# Battery_Manager.net
KiCad netlist of a schematic drawn in Altium Designer
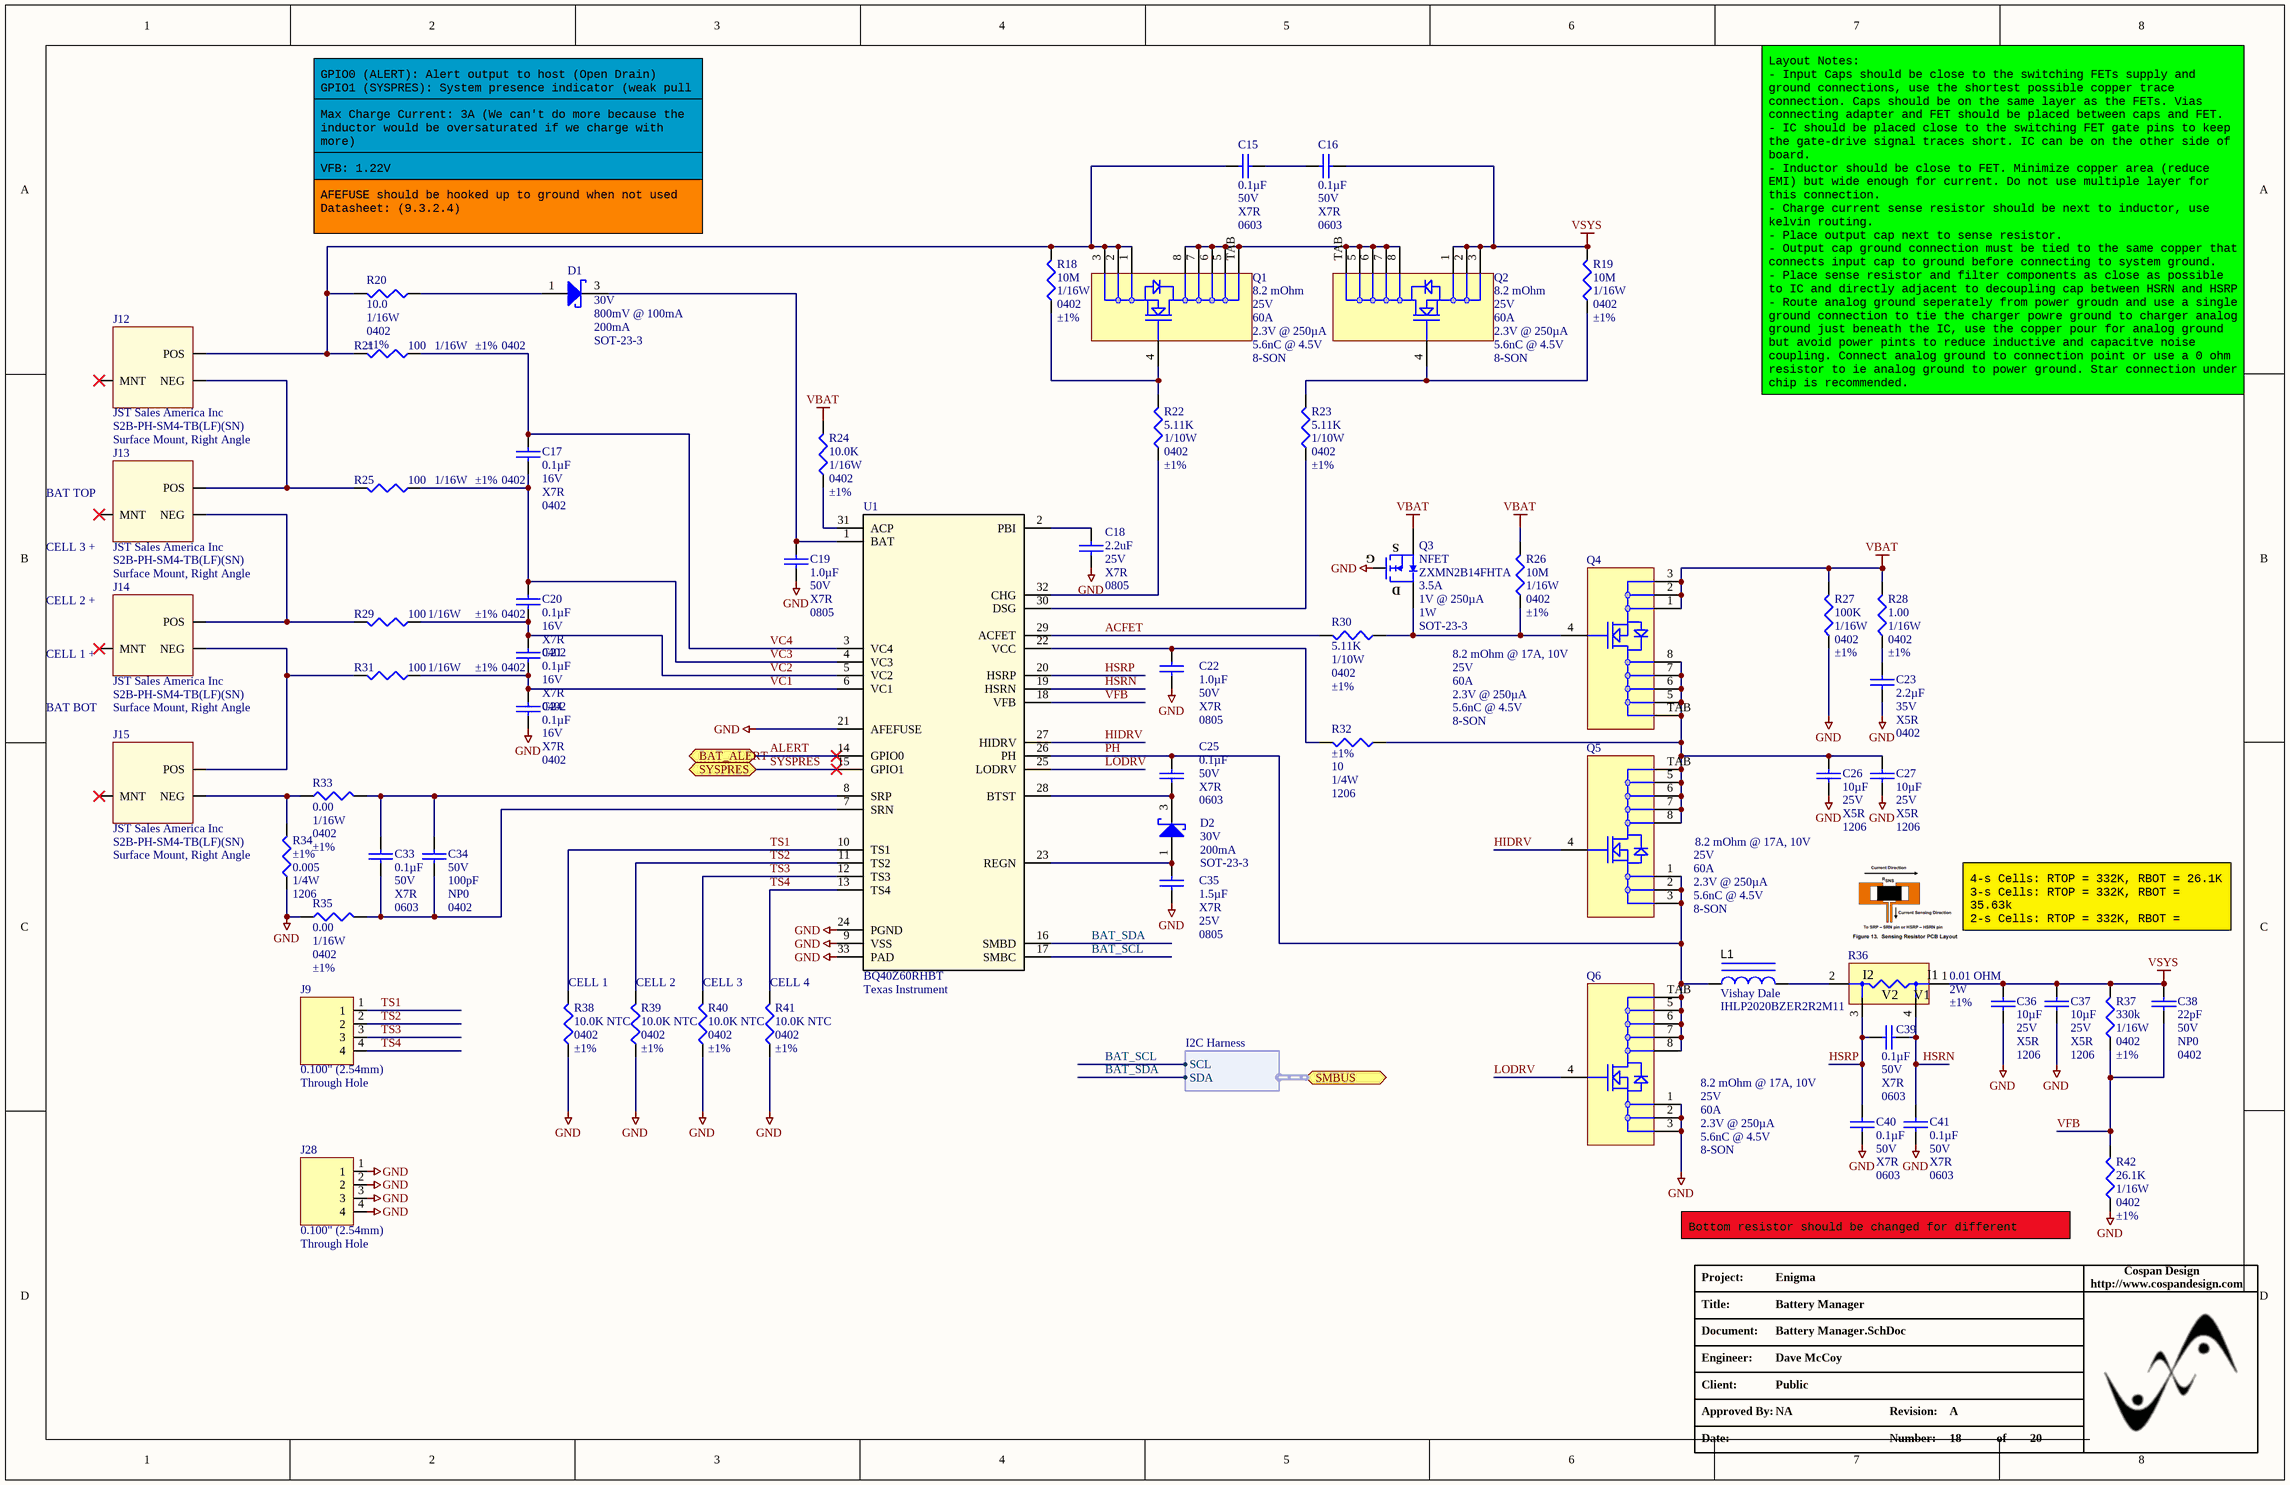
[diagram p0: Battery Manager.SchDoc]

(export (version "E")
  (design (tool "Eeschema 10.0.6"))
  (components
    (comp (ref "C15")
      (value "C_0603_0.1µF")
      (footprint "C_ERA-0603")
      (description "CAP CER 0.1UF 50V X7R 0603")
      (fields
        (field (name "MANUFACTURER") "Samsung Electro-Mechanics America, Inc.")
        (field (name "MANUFACTURER PART NUMBER") "CL10B104KB8SFNC")
        (field (name "CAPACITANCE") "0.1µF")
        (field (name "VOLTAGE - RATED") "50V")
        (field (name "TEMPERATURE COEFFICIENT") "X7R")
        (field (name "PACKAGE / CASE") "0603")
      )
      (libsource (lib "Cospan Design") (part "C_0603_0.1µF"))
    )
    (comp (ref "C16")
      (value "C_0603_0.1µF")
      (footprint "C_ERA-0603")
      (description "CAP CER 0.1UF 50V X7R 0603")
      (fields
        (field (name "MANUFACTURER") "Samsung Electro-Mechanics America, Inc.")
        (field (name "MANUFACTURER PART NUMBER") "CL10B104KB8SFNC")
        (field (name "CAPACITANCE") "0.1µF")
        (field (name "VOLTAGE - RATED") "50V")
        (field (name "TEMPERATURE COEFFICIENT") "X7R")
        (field (name "PACKAGE / CASE") "0603")
      )
      (libsource (lib "Cospan Design") (part "C_0603_0.1µF"))
    )
    (comp (ref "C17")
      (value "0.1uF")
      (footprint "C_0402")
      (description "CAP CER .10UF 16V X7R 0402")
      (fields
        (field (name "MANUFACTURER") "Murata Electronics North America")
        (field (name "MANUFACTURER PART NUMBER") "GRM155R71C104KA88J")
        (field (name "CAPACITANCE") "0.1µF")
        (field (name "VOLTAGE - RATED") "16V")
        (field (name "TEMPERATURE COEFFICIENT") "X7R")
        (field (name "PACKAGE / CASE") "0402")
      )
      (libsource (lib "Main LibraryX") (part "C_0402_0.1UF_16V"))
    )
    (comp (ref "C18")
      (value "C_0805_2.2uF_25V")
      (footprint "C_ERA-0805")
      (fields
        (field (name "MANUFACTURER") "Taiyo Yuden")
        (field (name "MANUFACTURER PART NUMBER") "TMK212B7225KG-TR")
        (field (name "TOLERANCE") "±10%")
        (field (name "CAPACITANCE") "2.2uF")
        (field (name "VOLTAGE - RATED") "25V")
        (field (name "TEMPERATURE COEFFICIENT") "X7R")
        (field (name "PACKAGE / CASE") "0805")
      )
      (libsource (lib "Cospan Design") (part "C_0805_2.2uF_25V"))
    )
    (comp (ref "C19")
      (value "1.0uF")
      (footprint "C_ERA-0805")
      (description "CAP CER 1UF 50V X7R 0805")
      (fields
        (field (name "MANUFACTURER") "Murata Electronics North America")
        (field (name "MANUFACTURER PART NUMBER") "GRM21BR71H105KA12L")
        (field (name "CAPACITANCE") "1.0µF")
        (field (name "VOLTAGE - RATED") "50V")
        (field (name "TEMPERATURE COEFFICIENT") "X7R")
        (field (name "PACKAGE / CASE") "0805")
      )
      (libsource (lib "Main Library") (part "C_0805_1.0uF_50V"))
    )
    (comp (ref "C20")
      (value "0.1uF")
      (footprint "C_0402")
      (description "CAP CER .10UF 16V X7R 0402")
      (fields
        (field (name "MANUFACTURER") "Murata Electronics North America")
        (field (name "MANUFACTURER PART NUMBER") "GRM155R71C104KA88J")
        (field (name "CAPACITANCE") "0.1µF")
        (field (name "VOLTAGE - RATED") "16V")
        (field (name "TEMPERATURE COEFFICIENT") "X7R")
        (field (name "PACKAGE / CASE") "0402")
      )
      (libsource (lib "Main LibraryX") (part "C_0402_0.1UF_16V"))
    )
    (comp (ref "C21")
      (value "0.1uF")
      (footprint "C_0402")
      (description "CAP CER .10UF 16V X7R 0402")
      (fields
        (field (name "MANUFACTURER") "Murata Electronics North America")
        (field (name "MANUFACTURER PART NUMBER") "GRM155R71C104KA88J")
        (field (name "CAPACITANCE") "0.1µF")
        (field (name "VOLTAGE - RATED") "16V")
        (field (name "TEMPERATURE COEFFICIENT") "X7R")
        (field (name "PACKAGE / CASE") "0402")
      )
      (libsource (lib "Main LibraryX") (part "C_0402_0.1UF_16V"))
    )
    (comp (ref "C22")
      (value "1.0uF")
      (footprint "C_ERA-0805")
      (description "CAP CER 1UF 50V X7R 0805")
      (fields
        (field (name "MANUFACTURER") "Murata Electronics North America")
        (field (name "MANUFACTURER PART NUMBER") "GRM21BR71H105KA12L")
        (field (name "CAPACITANCE") "1.0µF")
        (field (name "VOLTAGE - RATED") "50V")
        (field (name "TEMPERATURE COEFFICIENT") "X7R")
        (field (name "PACKAGE / CASE") "0805")
      )
      (libsource (lib "Main Library") (part "C_0805_1.0uF_50V"))
    )
    (comp (ref "C23")
      (value "C_0402_2.2uF_35V")
      (footprint "C_ERA-0402")
      (description "CAP CER 2.2UF 35V 20% X5R 0402")
      (fields
        (field (name "MANUFACTURER") "TDK Corporation")
        (field (name "MANUFACTURER PART NUMBER") "C1005X5R1V225K050BC")
        (field (name "CAPACITANCE") "2.2µF")
        (field (name "VOLTAGE - RATED") "35V")
        (field (name "TEMPERATURE COEFFICIENT") "X5R")
        (field (name "PACKAGE / CASE") "0402")
      )
      (libsource (lib "Main LibraryX") (part "C_0402_2.2uF_35V"))
    )
    (comp (ref "C24")
      (value "0.1uF")
      (footprint "C_0402")
      (description "CAP CER .10UF 16V X7R 0402")
      (fields
        (field (name "MANUFACTURER") "Murata Electronics North America")
        (field (name "MANUFACTURER PART NUMBER") "GRM155R71C104KA88J")
        (field (name "CAPACITANCE") "0.1µF")
        (field (name "VOLTAGE - RATED") "16V")
        (field (name "TEMPERATURE COEFFICIENT") "X7R")
        (field (name "PACKAGE / CASE") "0402")
      )
      (libsource (lib "Main LibraryX") (part "C_0402_0.1UF_16V"))
    )
    (comp (ref "C25")
      (value "C_0603_0.1µF")
      (footprint "C_ERA-0603")
      (description "CAP CER 0.1UF 50V X7R 0603")
      (fields
        (field (name "MANUFACTURER") "Samsung Electro-Mechanics America, Inc.")
        (field (name "MANUFACTURER PART NUMBER") "CL10B104KB8SFNC")
        (field (name "CAPACITANCE") "0.1µF")
        (field (name "VOLTAGE - RATED") "50V")
        (field (name "TEMPERATURE COEFFICIENT") "X7R")
        (field (name "PACKAGE / CASE") "0603")
      )
      (libsource (lib "Cospan Design") (part "C_0603_0.1µF"))
    )
    (comp (ref "C26")
      (value "10µF")
      (footprint "CAP-1206")
      (description "CAP CER 10UF 25V X5R 1206")
      (fields
        (field (name "MANUFACTURER") "Murata Electronics North America")
        (field (name "MANUFACTURER PART NUMBER") "GRM31CR61E106MA12L")
        (field (name "CAPACITANCE") "10µF")
        (field (name "VOLTAGE - RATED") "25V")
        (field (name "TEMPERATURE COEFFICIENT") "X5R")
        (field (name "PACKAGE / CASE") "1206")
      )
      (libsource (lib "Main Library") (part "C_1206_10UF_25V"))
    )
    (comp (ref "C27")
      (value "10µF")
      (footprint "CAP-1206")
      (description "CAP CER 10UF 25V X5R 1206")
      (fields
        (field (name "MANUFACTURER") "Murata Electronics North America")
        (field (name "MANUFACTURER PART NUMBER") "GRM31CR61E106MA12L")
        (field (name "CAPACITANCE") "10µF")
        (field (name "VOLTAGE - RATED") "25V")
        (field (name "TEMPERATURE COEFFICIENT") "X5R")
        (field (name "PACKAGE / CASE") "1206")
      )
      (libsource (lib "Main Library") (part "C_1206_10UF_25V"))
    )
    (comp (ref "C33")
      (value "C_0603_0.1µF")
      (footprint "C_ERA-0603")
      (description "CAP CER 0.1UF 50V X7R 0603")
      (fields
        (field (name "MANUFACTURER") "Samsung Electro-Mechanics America, Inc.")
        (field (name "MANUFACTURER PART NUMBER") "CL10B104KB8SFNC")
        (field (name "CAPACITANCE") "0.1µF")
        (field (name "VOLTAGE - RATED") "50V")
        (field (name "TEMPERATURE COEFFICIENT") "X7R")
        (field (name "PACKAGE / CASE") "0603")
      )
      (libsource (lib "Cospan Design") (part "C_0603_0.1µF"))
    )
    (comp (ref "C34")
      (value "100pF")
      (footprint "C_0402")
      (description "CAP CER 100PF 50V 5% C0G 0402")
      (fields
        (field (name "MANUFACTURER") "Murata Electronics North America")
        (field (name "MANUFACTURER PART NUMBER") "GRM1555C1H101JA01D")
        (field (name "VOLTAGE - RATED") "50V")
        (field (name "CAPACITANCE") "100pF")
        (field (name "TEMPERATURE COEFFICIENT") "NP0")
        (field (name "PACKAGE / CASE") "0402")
      )
      (libsource (lib "Main LibraryX") (part "C_0402_100PF"))
    )
    (comp (ref "C35")
      (value "C_0805_1.5uF_25V")
      (footprint "C_ERA-0805")
      (description "1.5µF ±10% 25V Ceramic Capacitor X7R 0805 (2012 Metric)")
      (fields
        (field (name "MANUFACTURER") "Murata Electronics North America")
        (field (name "MANUFACTURER PART NUMBER") "GRM21BR71E155KA88L")
        (field (name "CAPACITANCE") "1.5µF")
        (field (name "VOLTAGE - RATED") "X7R")
        (field (name "TEMPERATURE COEFFICIENT") "25V")
        (field (name "PACKAGE / CASE") "0805")
      )
      (libsource (lib "Cospan Design") (part "C_0805_1.5uF_25V"))
    )
    (comp (ref "C36")
      (value "10µF")
      (footprint "CAP-1206")
      (description "CAP CER 10UF 25V X5R 1206")
      (fields
        (field (name "MANUFACTURER") "Murata Electronics North America")
        (field (name "MANUFACTURER PART NUMBER") "GRM31CR61E106MA12L")
        (field (name "CAPACITANCE") "10µF")
        (field (name "VOLTAGE - RATED") "25V")
        (field (name "TEMPERATURE COEFFICIENT") "X5R")
        (field (name "PACKAGE / CASE") "1206")
      )
      (libsource (lib "Main Library") (part "C_1206_10UF_25V"))
    )
    (comp (ref "C37")
      (value "10µF")
      (footprint "CAP-1206")
      (description "CAP CER 10UF 25V X5R 1206")
      (fields
        (field (name "MANUFACTURER") "Murata Electronics North America")
        (field (name "MANUFACTURER PART NUMBER") "GRM31CR61E106MA12L")
        (field (name "CAPACITANCE") "10µF")
        (field (name "VOLTAGE - RATED") "25V")
        (field (name "TEMPERATURE COEFFICIENT") "X5R")
        (field (name "PACKAGE / CASE") "1206")
      )
      (libsource (lib "Main Library") (part "C_1206_10UF_25V"))
    )
    (comp (ref "C38")
      (value "22pF")
      (footprint "C_ERA-0402")
      (description "CAP CER 22PF 50V NP0 0402")
      (fields
        (field (name "MANUFACTURER") "Murata Electronics North America")
        (field (name "MANUFACTURER PART NUMBER") "GRM1555C1H220FA01D")
        (field (name "CAPACITANCE") "22pF")
        (field (name "VOLTAGE - RATED") "50V")
        (field (name "TEMPERATURE COEFFICIENT") "NP0")
        (field (name "PACKAGE / CASE") "0402")
      )
      (libsource (lib "Main LibraryX") (part "C_0402_22PF_50V"))
    )
    (comp (ref "C39")
      (value "C_0603_0.1µF")
      (footprint "C_ERA-0603")
      (description "CAP CER 0.1UF 50V X7R 0603")
      (fields
        (field (name "MANUFACTURER") "Samsung Electro-Mechanics America, Inc.")
        (field (name "MANUFACTURER PART NUMBER") "CL10B104KB8SFNC")
        (field (name "CAPACITANCE") "0.1µF")
        (field (name "VOLTAGE - RATED") "50V")
        (field (name "TEMPERATURE COEFFICIENT") "X7R")
        (field (name "PACKAGE / CASE") "0603")
      )
      (libsource (lib "Cospan Design") (part "C_0603_0.1µF"))
    )
    (comp (ref "C40")
      (value "C_0603_0.1µF")
      (footprint "C_ERA-0603")
      (description "CAP CER 0.1UF 50V X7R 0603")
      (fields
        (field (name "MANUFACTURER") "Samsung Electro-Mechanics America, Inc.")
        (field (name "MANUFACTURER PART NUMBER") "CL10B104KB8SFNC")
        (field (name "CAPACITANCE") "0.1µF")
        (field (name "VOLTAGE - RATED") "50V")
        (field (name "TEMPERATURE COEFFICIENT") "X7R")
        (field (name "PACKAGE / CASE") "0603")
      )
      (libsource (lib "Cospan Design") (part "C_0603_0.1µF"))
    )
    (comp (ref "C41")
      (value "C_0603_0.1µF")
      (footprint "C_ERA-0603")
      (description "CAP CER 0.1UF 50V X7R 0603")
      (fields
        (field (name "MANUFACTURER") "Samsung Electro-Mechanics America, Inc.")
        (field (name "MANUFACTURER PART NUMBER") "CL10B104KB8SFNC")
        (field (name "CAPACITANCE") "0.1µF")
        (field (name "VOLTAGE - RATED") "50V")
        (field (name "TEMPERATURE COEFFICIENT") "X7R")
        (field (name "PACKAGE / CASE") "0603")
      )
      (libsource (lib "Cospan Design") (part "C_0603_0.1µF"))
    )
    (comp (ref "D1")
      (value "BAT54")
      (footprint "SOT23")
      (description "DIODE SCHOTTKY 30V 200MA SOT-23")
      (fields
        (field (name "MANUFACTURER") "Fairchild Semiconductor")
        (field (name "VOLTAGE - DC REVERSE (VR) (MAX)") "30V")
        (field (name "VOLTAGE - FORWARD (VF) (MAX) @ IF") "800mV @ 100mA")
        (field (name "CURRENT - AVERAGE RECTIFIED (IO)") "200mA")
        (field (name "PACKAGE / CASE") "SOT-23-3")
      )
      (libsource (lib "Main Library") (part "D_SCHOTT_BAT54"))
    )
    (comp (ref "D2")
      (value "BAT54")
      (footprint "SOT23")
      (description "DIODE SCHOTTKY 30V 200MA SOT-23")
      (fields
        (field (name "MANUFACTURER") "Fairchild Semiconductor")
        (field (name "VOLTAGE - DC REVERSE (VR) (MAX)") "30V")
        (field (name "CURRENT - AVERAGE RECTIFIED (IO)") "200mA")
        (field (name "PACKAGE / CASE") "SOT-23-3")
      )
      (libsource (lib "Main Library") (part "D_SCHOTT_BAT54"))
    )
    (comp (ref "J9")
      (value "J_HDR1X4_THRHOLE_VERT")
      (footprint "HDR_1X4")
      (description "CONN HEADER .100\" 4POS TIN PCB")
      (fields
        (field (name "MANUFACTURER") "Samtec")
        (field (name "MANUFACTURER PART NUMBER") "TSW-104-07-T-S")
        (field (name "PITCH") "0.100\" (2.54mm)")
        (field (name "MOUNTING TYPE") "Through Hole")
      )
      (libsource (lib "Main Library") (part "J_HDR1X4_THRHOLE_VERT"))
    )
    (comp (ref "J12")
      (value "J_LIPO_BAT_CONNECTOR")
      (footprint "HDR_1X2_LIPO_BATTERY")
      (description "CONN HEADER PH SIDE 2POS 2MM SMD")
      (fields
        (field (name "MANUFACTURER") "JST Sales America Inc")
        (field (name "MANUFACTURER PART NUMBER") "S2B-PH-SM4-TB(LF)(SN)")
        (field (name "MOUNTING TYPE") "Surface Mount, Right Angle")
      )
      (libsource (lib "Main Library") (part "J_LIPO_BAT_CONNECTOR"))
    )
    (comp (ref "J13")
      (value "J_LIPO_BAT_CONNECTOR")
      (footprint "HDR_1X2_LIPO_BATTERY")
      (description "CONN HEADER PH SIDE 2POS 2MM SMD")
      (fields
        (field (name "MANUFACTURER") "JST Sales America Inc")
        (field (name "MANUFACTURER PART NUMBER") "S2B-PH-SM4-TB(LF)(SN)")
        (field (name "MOUNTING TYPE") "Surface Mount, Right Angle")
      )
      (libsource (lib "Main Library") (part "J_LIPO_BAT_CONNECTOR"))
    )
    (comp (ref "J14")
      (value "J_LIPO_BAT_CONNECTOR")
      (footprint "HDR_1X2_LIPO_BATTERY")
      (description "CONN HEADER PH SIDE 2POS 2MM SMD")
      (fields
        (field (name "MANUFACTURER") "JST Sales America Inc")
        (field (name "MANUFACTURER PART NUMBER") "S2B-PH-SM4-TB(LF)(SN)")
        (field (name "MOUNTING TYPE") "Surface Mount, Right Angle")
      )
      (libsource (lib "Main Library") (part "J_LIPO_BAT_CONNECTOR"))
    )
    (comp (ref "J15")
      (value "J_LIPO_BAT_CONNECTOR")
      (footprint "HDR_1X2_LIPO_BATTERY")
      (description "CONN HEADER PH SIDE 2POS 2MM SMD")
      (fields
        (field (name "MANUFACTURER") "JST Sales America Inc")
        (field (name "MANUFACTURER PART NUMBER") "S2B-PH-SM4-TB(LF)(SN)")
        (field (name "MOUNTING TYPE") "Surface Mount, Right Angle")
      )
      (libsource (lib "Main Library") (part "J_LIPO_BAT_CONNECTOR"))
    )
    (comp (ref "J28")
      (value "J_HDR1X4_THRHOLE_VERT")
      (footprint "HDR_1X4")
      (description "CONN HEADER .100\" 4POS TIN PCB")
      (fields
        (field (name "MANUFACTURER") "Samtec")
        (field (name "MANUFACTURER PART NUMBER") "TSW-104-07-T-S")
        (field (name "PITCH") "0.100\" (2.54mm)")
        (field (name "MOUNTING TYPE") "Through Hole")
      )
      (libsource (lib "Main Library") (part "J_HDR1X4_THRHOLE_VERT"))
    )
    (comp (ref "L1")
      (value "L_IHLP2020BZER2R2M11")
      (footprint "IHLP-2020BZ")
      (description "FIXED IND 2.2UH 5A 37.7 MOHM SMD")
      (fields
        (field (name "TOLERANCE") "±20%")
        (field (name "MANUFACTURER") "Vishay Dale")
        (field (name "MANUFACTURER PART NUMBER") "IHLP2020BZER2R2M11")
      )
      (libsource (lib "Cospan Design") (part "L_IHLP2020BZER2R2M11"))
    )
    (comp (ref "Q1")
      (value "N-Channel Nex_FET")
      (footprint "Q_TDSON-8 NexFET")
      (description "MOSFET N-CH 25V 60A 8-SON")
      (fields
        (field (name "MANUFACTURER") "Texas Instruments")
        (field (name "MANUFACTURER PART NUMBER") "CSD16409Q3")
        (field (name "RDS ON (MAX) @ ID, VGS") "8.2 mOhm")
        (field (name "DRAIN TO SOURCE VOLTAGE (VDSS)") "25V")
        (field (name "CURRENT - CONTINUOUS DRAIN (ID) @ 25° C") "60A")
        (field (name "VGS(TH) (MAX) @ ID") "2.3V @ 250µA")
        (field (name "GATE CHARGE (QG) @ VGS") "5.6nC @ 4.5V")
        (field (name "PACKAGE / CASE") "8-SON")
      )
      (libsource (lib "Main Library") (part "Q_N-CH_8SON_60A_9.5mOHM"))
    )
    (comp (ref "Q2")
      (value "N-Channel Nex_FET")
      (footprint "Q_TDSON-8 NexFET")
      (description "MOSFET N-CH 25V 60A 8-SON")
      (fields
        (field (name "MANUFACTURER") "Texas Instruments")
        (field (name "MANUFACTURER PART NUMBER") "CSD16409Q3")
        (field (name "RDS ON (MAX) @ ID, VGS") "8.2 mOhm")
        (field (name "DRAIN TO SOURCE VOLTAGE (VDSS)") "25V")
        (field (name "CURRENT - CONTINUOUS DRAIN (ID) @ 25° C") "60A")
        (field (name "VGS(TH) (MAX) @ ID") "2.3V @ 250µA")
        (field (name "GATE CHARGE (QG) @ VGS") "5.6nC @ 4.5V")
        (field (name "PACKAGE / CASE") "8-SON")
      )
      (libsource (lib "Main Library") (part "Q_N-CH_8SON_60A_9.5mOHM"))
    )
    (comp (ref "Q3")
      (value "NFET")
      (footprint "SOT-23A")
      (description "MOSFET N-CH 20V 3.5A SOT23-3")
      (fields
        (field (name "MANUFACTURER") "Diodes/Zetex")
        (field (name "MANUFACTURER PART NUMBER") "ZXMN2B14FHTA")
        (field (name "CURRENT - CONTINUOUS DRAIN (ID) @ 25° C") "3.5A")
        (field (name "VGS(TH) (MAX) @ ID") "1V @ 250µA")
        (field (name "POWER - MAX") "1W")
        (field (name "PACKAGE / CASE") "SOT-23-3")
      )
      (libsource (lib "Main LibraryX") (part "Q_NFET_3.50A_SOT23"))
    )
    (comp (ref "Q4")
      (value "N-Channel Nex_FET")
      (footprint "Q_TDSON-8 NexFET")
      (description "MOSFET N-CH 25V 60A 8-SON")
      (fields
        (field (name "MANUFACTURER") "Texas Instruments")
        (field (name "MANUFACTURER PART NUMBER") "CSD16409Q3")
        (field (name "RDS ON (MAX) @ ID, VGS") "8.2 mOhm @ 17A, 10V")
        (field (name "DRAIN TO SOURCE VOLTAGE (VDSS)") "25V")
        (field (name "CURRENT - CONTINUOUS DRAIN (ID) @ 25° C") "60A")
        (field (name "VGS(TH) (MAX) @ ID") "2.3V @ 250µA")
        (field (name "GATE CHARGE (QG) @ VGS") "5.6nC @ 4.5V")
        (field (name "PACKAGE / CASE") "8-SON")
      )
      (libsource (lib "Main Library") (part "Q_N-CH_8SON_60A_9.5mOHM"))
    )
    (comp (ref "Q5")
      (value "N-Channel Nex_FET")
      (footprint "Q_TDSON-8 NexFET")
      (description "MOSFET N-CH 25V 60A 8-SON")
      (fields
        (field (name "MANUFACTURER") "Texas Instruments")
        (field (name "MANUFACTURER PART NUMBER") "CSD16409Q3")
        (field (name "RDS ON (MAX) @ ID, VGS") "8.2 mOhm @ 17A, 10V")
        (field (name "DRAIN TO SOURCE VOLTAGE (VDSS)") "25V")
        (field (name "CURRENT - CONTINUOUS DRAIN (ID) @ 25° C") "60A")
        (field (name "VGS(TH) (MAX) @ ID") "2.3V @ 250µA")
        (field (name "GATE CHARGE (QG) @ VGS") "5.6nC @ 4.5V")
        (field (name "PACKAGE / CASE") "8-SON")
      )
      (libsource (lib "Main Library") (part "Q_N-CH_8SON_60A_9.5mOHM"))
    )
    (comp (ref "Q6")
      (value "N-Channel Nex_FET")
      (footprint "Q_TDSON-8 NexFET")
      (description "MOSFET N-CH 25V 60A 8-SON")
      (fields
        (field (name "MANUFACTURER") "Texas Instruments")
        (field (name "MANUFACTURER PART NUMBER") "CSD16409Q3")
        (field (name "RDS ON (MAX) @ ID, VGS") "8.2 mOhm @ 17A, 10V")
        (field (name "DRAIN TO SOURCE VOLTAGE (VDSS)") "25V")
        (field (name "CURRENT - CONTINUOUS DRAIN (ID) @ 25° C") "60A")
        (field (name "VGS(TH) (MAX) @ ID") "2.3V @ 250µA")
        (field (name "GATE CHARGE (QG) @ VGS") "5.6nC @ 4.5V")
        (field (name "PACKAGE / CASE") "8-SON")
      )
      (libsource (lib "Main Library") (part "Q_N-CH_8SON_60A_9.5mOHM"))
    )
    (comp (ref "R18")
      (value "R_0402_10M")
      (footprint "R_0402")
      (description "RES SMD 10M OHM 1% 1/16W 0402")
      (fields
        (field (name "MANUFACTURER") "Yageo")
        (field (name "MANUFACTURER PART NUMBER") "RC0402FR-0710ML")
        (field (name "RESISTANCE IN OHMS") "10M")
        (field (name "POWER (WATTS)") "1/16W")
        (field (name "CASE") "0402")
        (field (name "TOLERANCE") "±1%")
      )
      (libsource (lib "Cospan Design") (part "R_0402_10M"))
    )
    (comp (ref "R19")
      (value "R_0402_10M")
      (footprint "R_0402")
      (description "RES SMD 10M OHM 1% 1/16W 0402")
      (fields
        (field (name "MANUFACTURER") "Yageo")
        (field (name "MANUFACTURER PART NUMBER") "RC0402FR-0710ML")
        (field (name "RESISTANCE IN OHMS") "10M")
        (field (name "POWER (WATTS)") "1/16W")
        (field (name "CASE") "0402")
        (field (name "TOLERANCE") "±1%")
      )
      (libsource (lib "Cospan Design") (part "R_0402_10M"))
    )
    (comp (ref "R20")
      (value "R_0402_10.0")
      (footprint "R_0402")
      (description "RES 10.0 OHM 1/16W 1% 0402 SMD")
      (fields
        (field (name "MANUFACTURER") "Yageo")
        (field (name "MANUFACTURER PART NUMBER") "RC0402FR-0710RL")
        (field (name "RESISTANCE IN OHMS") "10.0")
        (field (name "POWER (WATTS)") "1/16W")
        (field (name "CASE") "0402")
        (field (name "TOLERANCE") "±1%")
      )
      (libsource (lib "Main LibraryX") (part "R_0402_10.0"))
    )
    (comp (ref "R21")
      (value "R_0402_100.0")
      (footprint "R_0402")
      (description "RES 100 OHM 1/16W 1% 0402 SMD")
      (fields
        (field (name "MANUFACTURER") "Yageo")
        (field (name "MANUFACTURER PART NUMBER") "RC0402FR-07100RL")
        (field (name "CASE") "0402")
        (field (name "RESISTANCE IN OHMS") "100")
        (field (name "POWER (WATTS)") "1/16W")
        (field (name "TOLERANCE") "±1%")
      )
      (libsource (lib "Main LibraryX") (part "R_0402_100.0"))
    )
    (comp (ref "R22")
      (value "5.11k Ohms")
      (footprint "R_0402")
      (description "RES 5.11K OHM 1/10W 1% 0402 SMD")
      (fields
        (field (name "MANUFACTURER") "Panasonic - ECG")
        (field (name "MANUFACTURER PART NUMBER") "ERJ-2RKF5111X")
        (field (name "RESISTANCE IN OHMS") "5.11K")
        (field (name "POWER (WATTS)") "1/10W")
        (field (name "CASE") "0402")
        (field (name "TOLERANCE") "±1%")
      )
      (libsource (lib "Main Library") (part "R_0402_5.11K"))
    )
    (comp (ref "R23")
      (value "5.11k Ohms")
      (footprint "R_0402")
      (description "RES 5.11K OHM 1/10W 1% 0402 SMD")
      (fields
        (field (name "MANUFACTURER") "Panasonic - ECG")
        (field (name "MANUFACTURER PART NUMBER") "ERJ-2RKF5111X")
        (field (name "RESISTANCE IN OHMS") "5.11K")
        (field (name "POWER (WATTS)") "1/10W")
        (field (name "CASE") "0402")
        (field (name "TOLERANCE") "±1%")
      )
      (libsource (lib "Main Library") (part "R_0402_5.11K"))
    )
    (comp (ref "R24")
      (value "R_0402_10.0K")
      (footprint "R_0402")
      (description "RES 10.0K OHM 1/16W 1% 0402 SMD")
      (fields
        (field (name "MANUFACTURER") "Stackpole Electronics Inc")
        (field (name "MANUFACTURER PART NUMBER") "RMCF0402FT10K0")
        (field (name "RESISTANCE IN OHMS") "10.0K")
        (field (name "POWER (WATTS)") "1/16W")
        (field (name "CASE") "0402")
        (field (name "TOLERANCE") "±1%")
      )
      (libsource (lib "Main Library") (part "R_0402_10.0K"))
    )
    (comp (ref "R25")
      (value "R_0402_100.0")
      (footprint "R_0402")
      (description "RES 100 OHM 1/16W 1% 0402 SMD")
      (fields
        (field (name "MANUFACTURER") "Yageo")
        (field (name "MANUFACTURER PART NUMBER") "RC0402FR-07100RL")
        (field (name "CASE") "0402")
        (field (name "RESISTANCE IN OHMS") "100")
        (field (name "POWER (WATTS)") "1/16W")
        (field (name "TOLERANCE") "±1%")
      )
      (libsource (lib "Main LibraryX") (part "R_0402_100.0"))
    )
    (comp (ref "R26")
      (value "R_0402_10M")
      (footprint "R_0402")
      (description "RES SMD 10M OHM 1% 1/16W 0402")
      (fields
        (field (name "MANUFACTURER") "Yageo")
        (field (name "MANUFACTURER PART NUMBER") "RC0402FR-0710ML")
        (field (name "RESISTANCE IN OHMS") "10M")
        (field (name "POWER (WATTS)") "1/16W")
        (field (name "CASE") "0402")
        (field (name "TOLERANCE") "±1%")
      )
      (libsource (lib "Cospan Design") (part "R_0402_10M"))
    )
    (comp (ref "R27")
      (value "R_0402_100.0K")
      (footprint "R_0402")
      (description "RES 100K OHM 1/16W 1% 0402 SMD")
      (fields
        (field (name "MANUFACTURER") "Stackpole Electronics Inc")
        (field (name "MANUFACTURER PART NUMBER") "RMCF0402FT100K")
        (field (name "RESISTANCE IN OHMS") "100K")
        (field (name "POWER (WATTS)") "1/16W")
        (field (name "CASE") "0402")
        (field (name "TOLERANCE") "±1%")
      )
      (libsource (lib "Main Library") (part "R_0402_100.0K"))
    )
    (comp (ref "R28")
      (value "1.0 Ohms")
      (footprint "R_0402")
      (description "RES 1.00 OHM 1/16W 1% 0402 SMD")
      (fields
        (field (name "MANUFACTURER") "Yageo")
        (field (name "MANUFACTURER PART NUMBER") "RC0402FR-071RL")
        (field (name "RESISTANCE IN OHMS") "1.00")
        (field (name "POWER (WATTS)") "1/16W")
        (field (name "CASE") "0402")
        (field (name "TOLERANCE") "±1%")
      )
      (libsource (lib "Main Library") (part "R_0402_1.00"))
    )
    (comp (ref "R29")
      (value "R_0402_100.0")
      (footprint "R_0402")
      (description "RES 100 OHM 1/16W 1% 0402 SMD")
      (fields
        (field (name "MANUFACTURER") "Yageo")
        (field (name "MANUFACTURER PART NUMBER") "RC0402FR-07100RL")
        (field (name "CASE") "0402")
        (field (name "RESISTANCE IN OHMS") "100")
        (field (name "POWER (WATTS)") "1/16W")
        (field (name "TOLERANCE") "±1%")
      )
      (libsource (lib "Main LibraryX") (part "R_0402_100.0"))
    )
    (comp (ref "R30")
      (value "5.11k Ohms")
      (footprint "R_0402")
      (description "RES 5.11K OHM 1/10W 1% 0402 SMD")
      (fields
        (field (name "MANUFACTURER") "Panasonic - ECG")
        (field (name "MANUFACTURER PART NUMBER") "ERJ-2RKF5111X")
        (field (name "RESISTANCE IN OHMS") "5.11K")
        (field (name "POWER (WATTS)") "1/10W")
        (field (name "CASE") "0402")
        (field (name "TOLERANCE") "±1%")
      )
      (libsource (lib "Main Library") (part "R_0402_5.11K"))
    )
    (comp (ref "R31")
      (value "R_0402_100.0")
      (footprint "R_0402")
      (description "RES 100 OHM 1/16W 1% 0402 SMD")
      (fields
        (field (name "MANUFACTURER") "Yageo")
        (field (name "MANUFACTURER PART NUMBER") "RC0402FR-07100RL")
        (field (name "CASE") "0402")
        (field (name "RESISTANCE IN OHMS") "100")
        (field (name "POWER (WATTS)") "1/16W")
        (field (name "TOLERANCE") "±1%")
      )
      (libsource (lib "Main LibraryX") (part "R_0402_100.0"))
    )
    (comp (ref "R32")
      (value "R_1206_10")
      (footprint "R_1206")
      (description "RES SMD 10 OHM 1% 1/4W 1206")
      (fields
        (field (name "MANUFACTURER") "Yageo")
        (field (name "MANUFACTURER PART NUMBER") "RC1206FR-0710RL")
        (field (name "TOLERANCE") "±1%")
        (field (name "RESISTANCE IN OHMS") "10")
        (field (name "POWER (WATTS)") "1/4W")
        (field (name "CASE") "1206")
      )
      (libsource (lib "Cospan Design") (part "R_1206_10"))
    )
    (comp (ref "R33")
      (value "0.0 Ohms")
      (footprint "R_0402")
      (description "RES SMD 0.0OHM JUMPER 1/10W 0402")
      (fields
        (field (name "MANUFACTURER") "Panasonic - ECG")
        (field (name "MANUFACTURER PART NUMBER") "ERJ-2GE0R00X")
        (field (name "RESISTANCE IN OHMS") "0.00")
        (field (name "POWER (WATTS)") "1/16W")
        (field (name "CASE") "0402")
        (field (name "TOLERANCE") "±1%")
      )
      (libsource (lib "Main LibraryX") (part "R_0402_0.00"))
    )
    (comp (ref "R34")
      (value "R_1206_0.005")
      (footprint "R_1206")
      (description "RES SMD 0.005 OHM 1% 1W 1206")
      (fields
        (field (name "MANUFACTURER") "Stackpole Electronics Inc.")
        (field (name "MANUFACTURER PART NUMBER") "CSRF1206FT5L00")
        (field (name "TOLERANCE") "±1%")
        (field (name "RESISTANCE IN OHMS") "0.005")
        (field (name "POWER (WATTS)") "1/4W")
        (field (name "CASE") "1206")
      )
      (libsource (lib "Cospan Design") (part "R_1206_0.005"))
    )
    (comp (ref "R35")
      (value "0.0 Ohms")
      (footprint "R_0402")
      (description "RES SMD 0.0OHM JUMPER 1/10W 0402")
      (fields
        (field (name "MANUFACTURER") "Panasonic - ECG")
        (field (name "MANUFACTURER PART NUMBER") "ERJ-2GE0R00X")
        (field (name "RESISTANCE IN OHMS") "0.00")
        (field (name "POWER (WATTS)") "1/16W")
        (field (name "CASE") "0402")
        (field (name "TOLERANCE") "±1%")
      )
      (libsource (lib "Main LibraryX") (part "R_0402_0.00"))
    )
    (comp (ref "R36")
      (value "0.01 OHM")
      (footprint "R_LVK25_0.003")
      (description "RES SMD 0.01 OHM 1% 2W 1224")
      (fields
        (field (name "MANUFACTURER") "Ohmite")
        (field (name "MANUFACTURER PART NUMBER") "LVK25R010FER")
        (field (name "POWER (WATTS)") "2W")
        (field (name "TOLERANCE") "±1%")
      )
      (libsource (lib "Main Library") (part "R_0.010SENSE_LK20"))
    )
    (comp (ref "R37")
      (value "R_0402_330K")
      (footprint "R_0402")
      (description "RES SMD 330K OHM 1% 1/16W 0402")
      (fields
        (field (name "MANUFACTURER") "Yageo")
        (field (name "MANUFACTURER PART NUMBER") "RC0402FR-07330KL")
        (field (name "RESISTANCE IN OHMS") "330k")
        (field (name "POWER (WATTS)") "1/16W")
        (field (name "CASE") "0402")
        (field (name "TOLERANCE") "±1%")
      )
      (libsource (lib "Cospan Design") (part "R_0402_330K"))
    )
    (comp (ref "R38")
      (value "R_0402_NTC_10.0K")
      (footprint "R_0402")
      (description "NTC Thermistor 10k 0402 (1005 Metric)")
      (fields
        (field (name "MANUFACTURER") "Murata Electronics North America")
        (field (name "MANUFACTURER PART NUMBER") "NCP15XH103F03RC")
        (field (name "RESISTANCE IN OHMS") "10.0K NTC")
        (field (name "CASE") "0402")
        (field (name "TOLERANCE") "±1%")
      )
      (libsource (lib "Cospan Design") (part "R_0402_NTC_10.0K"))
    )
    (comp (ref "R39")
      (value "R_0402_NTC_10.0K")
      (footprint "R_0402")
      (description "NTC Thermistor 10k 0402 (1005 Metric)")
      (fields
        (field (name "MANUFACTURER") "Murata Electronics North America")
        (field (name "MANUFACTURER PART NUMBER") "NCP15XH103F03RC")
        (field (name "RESISTANCE IN OHMS") "10.0K NTC")
        (field (name "CASE") "0402")
        (field (name "TOLERANCE") "±1%")
      )
      (libsource (lib "Cospan Design") (part "R_0402_NTC_10.0K"))
    )
    (comp (ref "R40")
      (value "R_0402_NTC_10.0K")
      (footprint "R_0402")
      (description "NTC Thermistor 10k 0402 (1005 Metric)")
      (fields
        (field (name "MANUFACTURER") "Murata Electronics North America")
        (field (name "MANUFACTURER PART NUMBER") "NCP15XH103F03RC")
        (field (name "RESISTANCE IN OHMS") "10.0K NTC")
        (field (name "CASE") "0402")
        (field (name "TOLERANCE") "±1%")
      )
      (libsource (lib "Cospan Design") (part "R_0402_NTC_10.0K"))
    )
    (comp (ref "R41")
      (value "R_0402_NTC_10.0K")
      (footprint "R_0402")
      (description "NTC Thermistor 10k 0402 (1005 Metric)")
      (fields
        (field (name "MANUFACTURER") "Murata Electronics North America")
        (field (name "MANUFACTURER PART NUMBER") "NCP15XH103F03RC")
        (field (name "RESISTANCE IN OHMS") "10.0K NTC")
        (field (name "CASE") "0402")
        (field (name "TOLERANCE") "±1%")
      )
      (libsource (lib "Cospan Design") (part "R_0402_NTC_10.0K"))
    )
    (comp (ref "R42")
      (value "R_0402_26.1K")
      (footprint "R_0402")
      (description "RES SMD 26.1K OHM 1% 1/16W 0402")
      (fields
        (field (name "MANUFACTURER") "Stackpole Electronics Inc.")
        (field (name "MANUFACTURER PART NUMBER") "RMCF0402FT26K1")
        (field (name "RESISTANCE IN OHMS") "26.1K")
        (field (name "POWER (WATTS)") "1/16W")
        (field (name "CASE") "0402")
        (field (name "TOLERANCE") "±1%")
      )
      (libsource (lib "Cospan Design") (part "R_0402_26.1K"))
    )
    (comp (ref "U1")
      (value "U_BQ40Z60RHBR")
      (footprint "RHB0032E")
      (description "IC BATTERY MANAGER 32VQFN")
      (fields
        (field (name "MANUFACTURER PART NUMBER") "BQ40Z60RHBT")
        (field (name "MANUFACTURER") "Texas Instrument")
      )
      (libsource (lib "Cospan Design") (part "U_BQ40Z60RHBR"))
    )
  )
  (nets
    (net (code "3") (name "/ACFET") (class "Default")
      (node (ref "R30") (pin "1") (pinfunction "1_1") (pintype "passive"))
      (node (ref "U1") (pin "29") (pinfunction "ACFET_29") (pintype "passive"))
    )
    (net (code "4") (name "/ALERT") (class "Default")
      (node (ref "U1") (pin "14") (pinfunction "GPIO0_14") (pintype "passive+no_connect"))
    )
    (net (code "5") (name "/BAT_SCL") (class "Default")
      (node (ref "U1") (pin "17") (pinfunction "SMBC_17") (pintype "passive"))
    )
    (net (code "6") (name "/BAT_SDA") (class "Default")
      (node (ref "U1") (pin "16") (pinfunction "SMBD_16") (pintype "passive"))
    )
    (net (code "7") (name "/HIDRV") (class "Default")
      (node (ref "Q5") (pin "4") (pinfunction "G1_4") (pintype "passive"))
      (node (ref "U1") (pin "27") (pinfunction "HIDRV_27") (pintype "passive"))
    )
    (net (code "8") (name "/HSRN") (class "Default")
      (node (ref "C39") (pin "2") (pinfunction "2_2") (pintype "passive"))
      (node (ref "C41") (pin "1") (pinfunction "1_1") (pintype "passive"))
      (node (ref "R36") (pin "4") (pinfunction "V1_4") (pintype "passive"))
      (node (ref "U1") (pin "19") (pinfunction "HSRN_19") (pintype "passive"))
    )
    (net (code "9") (name "/HSRP") (class "Default")
      (node (ref "C39") (pin "1") (pinfunction "1_1") (pintype "passive"))
      (node (ref "C40") (pin "1") (pinfunction "1_1") (pintype "passive"))
      (node (ref "R36") (pin "3") (pinfunction "V2_3") (pintype "passive"))
      (node (ref "U1") (pin "20") (pinfunction "HSRP_20") (pintype "passive"))
    )
    (net (code "10") (name "/LODRV") (class "Default")
      (node (ref "Q6") (pin "4") (pinfunction "G1_4") (pintype "passive"))
      (node (ref "U1") (pin "25") (pinfunction "LODRV_25") (pintype "passive"))
    )
    (net (code "11") (name "/PH") (class "Default")
      (node (ref "C25") (pin "1") (pinfunction "1_1") (pintype "passive"))
      (node (ref "L1") (pin "2") (pinfunction "2_2") (pintype "passive"))
      (node (ref "Q5") (pin "1") (pinfunction "S1_1") (pintype "passive"))
      (node (ref "Q5") (pin "2") (pintype "passive"))
      (node (ref "Q5") (pin "3") (pintype "passive"))
      (node (ref "Q6") (pin "5") (pintype "passive"))
      (node (ref "Q6") (pin "6") (pintype "passive"))
      (node (ref "Q6") (pin "7") (pinfunction "D2a_7") (pintype "passive"))
      (node (ref "Q6") (pin "8") (pinfunction "D2b_8") (pintype "passive"))
      (node (ref "Q6") (pin "TAB") (pintype "passive"))
      (node (ref "U1") (pin "26") (pinfunction "PH_26") (pintype "passive"))
    )
    (net (code "12") (name "/SYSPRES") (class "Default")
      (node (ref "U1") (pin "15") (pinfunction "GPIO1_15") (pintype "passive+no_connect"))
    )
    (net (code "13") (name "/TS1") (class "Default")
      (node (ref "J9") (pin "1") (pinfunction "1_1") (pintype "passive"))
      (node (ref "R38") (pin "1") (pinfunction "1_1") (pintype "passive"))
      (node (ref "U1") (pin "10") (pinfunction "TS1_10") (pintype "passive"))
    )
    (net (code "14") (name "/TS2") (class "Default")
      (node (ref "J9") (pin "2") (pinfunction "2_2") (pintype "passive"))
      (node (ref "R39") (pin "1") (pinfunction "1_1") (pintype "passive"))
      (node (ref "U1") (pin "11") (pinfunction "TS2_11") (pintype "passive"))
    )
    (net (code "15") (name "/TS3") (class "Default")
      (node (ref "J9") (pin "3") (pinfunction "3_3") (pintype "passive"))
      (node (ref "R40") (pin "1") (pinfunction "1_1") (pintype "passive"))
      (node (ref "U1") (pin "12") (pinfunction "TS3_12") (pintype "passive"))
    )
    (net (code "16") (name "/TS4") (class "Default")
      (node (ref "J9") (pin "4") (pinfunction "4_4") (pintype "passive"))
      (node (ref "R41") (pin "1") (pinfunction "1_1") (pintype "passive"))
      (node (ref "U1") (pin "13") (pinfunction "TS4_13") (pintype "passive"))
    )
    (net (code "17") (name "/VC1") (class "Default")
      (node (ref "C21") (pin "2") (pinfunction "2_2") (pintype "passive"))
      (node (ref "C24") (pin "1") (pinfunction "1_1") (pintype "passive"))
      (node (ref "R31") (pin "2") (pinfunction "2_2") (pintype "passive"))
      (node (ref "U1") (pin "6") (pinfunction "VC1_6") (pintype "passive"))
    )
    (net (code "18") (name "/VC2") (class "Default")
      (node (ref "C20") (pin "2") (pinfunction "2_2") (pintype "passive"))
      (node (ref "C21") (pin "1") (pinfunction "1_1") (pintype "passive"))
      (node (ref "R29") (pin "2") (pinfunction "2_2") (pintype "passive"))
      (node (ref "U1") (pin "5") (pinfunction "VC2_5") (pintype "passive"))
    )
    (net (code "19") (name "/VC3") (class "Default")
      (node (ref "C17") (pin "2") (pinfunction "2_2") (pintype "passive"))
      (node (ref "C20") (pin "1") (pinfunction "1_1") (pintype "passive"))
      (node (ref "R25") (pin "2") (pinfunction "2_2") (pintype "passive"))
      (node (ref "U1") (pin "4") (pinfunction "VC3_4") (pintype "passive"))
    )
    (net (code "20") (name "/VC4") (class "Default")
      (node (ref "C17") (pin "1") (pinfunction "1_1") (pintype "passive"))
      (node (ref "R21") (pin "2") (pinfunction "2_2") (pintype "passive"))
      (node (ref "U1") (pin "3") (pinfunction "VC4_3") (pintype "passive"))
    )
    (net (code "21") (name "/VFB") (class "Default")
      (node (ref "C38") (pin "1") (pinfunction "1_1") (pintype "passive"))
      (node (ref "R37") (pin "2") (pinfunction "2_2") (pintype "passive"))
      (node (ref "R42") (pin "1") (pinfunction "1_1") (pintype "passive"))
      (node (ref "U1") (pin "18") (pinfunction "VFB_18") (pintype "passive"))
    )
    (net (code "23") (name "GND") (class "Default")
      (node (ref "C18") (pin "1") (pinfunction "1_1") (pintype "passive"))
      (node (ref "C19") (pin "1") (pinfunction "1_1") (pintype "passive"))
      (node (ref "C22") (pin "1") (pinfunction "1_1") (pintype "passive"))
      (node (ref "C23") (pin "1") (pinfunction "1_1") (pintype "passive"))
      (node (ref "C24") (pin "2") (pinfunction "2_2") (pintype "passive"))
      (node (ref "C26") (pin "1") (pinfunction "1_1") (pintype "passive"))
      (node (ref "C27") (pin "1") (pinfunction "1_1") (pintype "passive"))
      (node (ref "C35") (pin "1") (pinfunction "1_1") (pintype "passive"))
      (node (ref "C36") (pin "2") (pinfunction "2_2") (pintype "passive"))
      (node (ref "C37") (pin "2") (pinfunction "2_2") (pintype "passive"))
      (node (ref "C40") (pin "2") (pinfunction "2_2") (pintype "passive"))
      (node (ref "C41") (pin "2") (pinfunction "2_2") (pintype "passive"))
      (node (ref "J28") (pin "1") (pinfunction "1_1") (pintype "passive"))
      (node (ref "J28") (pin "2") (pinfunction "2_2") (pintype "passive"))
      (node (ref "J28") (pin "3") (pinfunction "3_3") (pintype "passive"))
      (node (ref "J28") (pin "4") (pinfunction "4_4") (pintype "passive"))
      (node (ref "Q3") (pin "1") (pinfunction "G_1") (pintype "passive"))
      (node (ref "Q6") (pin "1") (pinfunction "S1_1") (pintype "passive"))
      (node (ref "Q6") (pin "2") (pintype "passive"))
      (node (ref "Q6") (pin "3") (pintype "passive"))
      (node (ref "R27") (pin "2") (pinfunction "2_2") (pintype "passive"))
      (node (ref "R34") (pin "2") (pinfunction "2_2") (pintype "passive"))
      (node (ref "R35") (pin "2") (pinfunction "2_2") (pintype "passive"))
      (node (ref "R38") (pin "2") (pinfunction "2_2") (pintype "passive"))
      (node (ref "R39") (pin "2") (pinfunction "2_2") (pintype "passive"))
      (node (ref "R40") (pin "2") (pinfunction "2_2") (pintype "passive"))
      (node (ref "R41") (pin "2") (pinfunction "2_2") (pintype "passive"))
      (node (ref "R42") (pin "2") (pinfunction "2_2") (pintype "passive"))
      (node (ref "U1") (pin "21") (pinfunction "AFEFUSE_21") (pintype "passive"))
      (node (ref "U1") (pin "24") (pinfunction "PGND_24") (pintype "passive"))
      (node (ref "U1") (pin "33") (pinfunction "PAD_33") (pintype "passive"))
      (node (ref "U1") (pin "9") (pinfunction "VSS_9") (pintype "passive"))
    )
    (net (code "24") (name "Net-(C15-Pad1)") (class "Default")
      (node (ref "C15") (pin "1") (pinfunction "1_1") (pintype "passive"))
      (node (ref "C16") (pin "2") (pinfunction "2_2") (pintype "passive"))
    )
    (net (code "25") (name "Net-(C23-Pad2)") (class "Default")
      (node (ref "C23") (pin "2") (pinfunction "2_2") (pintype "passive"))
      (node (ref "R28") (pin "2") (pinfunction "2_2") (pintype "passive"))
    )
    (net (code "26") (name "Net-(D1-A)") (class "Default")
      (node (ref "D1") (pin "1") (pinfunction "A_1") (pintype "passive"))
      (node (ref "R20") (pin "2") (pinfunction "2_2") (pintype "passive"))
    )
    (net (code "27") (name "Net-(D1-K)") (class "Default")
      (node (ref "C19") (pin "2") (pinfunction "2_2") (pintype "passive"))
      (node (ref "D1") (pin "3") (pinfunction "K_3") (pintype "passive"))
      (node (ref "U1") (pin "1") (pinfunction "BAT_1") (pintype "passive"))
    )
    (net (code "28") (name "Net-(D2-A)") (class "Default")
      (node (ref "C35") (pin "2") (pinfunction "2_2") (pintype "passive"))
      (node (ref "D2") (pin "1") (pinfunction "A_1") (pintype "passive"))
      (node (ref "U1") (pin "23") (pinfunction "REGN_23") (pintype "passive"))
    )
    (net (code "29") (name "Net-(D2-K)") (class "Default")
      (node (ref "C25") (pin "2") (pinfunction "2_2") (pintype "passive"))
      (node (ref "D2") (pin "3") (pinfunction "K_3") (pintype "passive"))
      (node (ref "U1") (pin "28") (pinfunction "BTST_28") (pintype "passive"))
    )
    (net (code "30") (name "Net-(J12-NEG)") (class "Default")
      (node (ref "J12") (pin "2") (pinfunction "NEG_2") (pintype "passive"))
      (node (ref "J13") (pin "1") (pinfunction "POS_1") (pintype "passive"))
      (node (ref "R25") (pin "1") (pinfunction "1_1") (pintype "passive"))
    )
    (net (code "31") (name "Net-(J12-POS)") (class "Default")
      (node (ref "C15") (pin "2") (pinfunction "2_2") (pintype "passive"))
      (node (ref "J12") (pin "1") (pinfunction "POS_1") (pintype "passive"))
      (node (ref "Q1") (pin "1") (pinfunction "S1_1") (pintype "passive"))
      (node (ref "Q1") (pin "2") (pintype "passive"))
      (node (ref "Q1") (pin "3") (pintype "passive"))
      (node (ref "R18") (pin "1") (pinfunction "1_1") (pintype "passive"))
      (node (ref "R20") (pin "1") (pinfunction "1_1") (pintype "passive"))
      (node (ref "R21") (pin "1") (pinfunction "1_1") (pintype "passive"))
    )
    (net (code "32") (name "Net-(J13-NEG)") (class "Default")
      (node (ref "J13") (pin "2") (pinfunction "NEG_2") (pintype "passive"))
      (node (ref "J14") (pin "1") (pinfunction "POS_1") (pintype "passive"))
      (node (ref "R29") (pin "1") (pinfunction "1_1") (pintype "passive"))
    )
    (net (code "33") (name "Net-(J14-NEG)") (class "Default")
      (node (ref "J14") (pin "2") (pinfunction "NEG_2") (pintype "passive"))
      (node (ref "J15") (pin "1") (pinfunction "POS_1") (pintype "passive"))
      (node (ref "R31") (pin "1") (pinfunction "1_1") (pintype "passive"))
    )
    (net (code "34") (name "Net-(J15-NEG)") (class "Default")
      (node (ref "J15") (pin "2") (pinfunction "NEG_2") (pintype "passive"))
      (node (ref "R33") (pin "2") (pinfunction "2_2") (pintype "passive"))
      (node (ref "R34") (pin "1") (pinfunction "1_1") (pintype "passive"))
    )
    (net (code "35") (name "Net-(Q1-D2a)") (class "Default")
      (node (ref "Q1") (pin "5") (pintype "passive"))
      (node (ref "Q1") (pin "6") (pintype "passive"))
      (node (ref "Q1") (pin "7") (pinfunction "D2a_7") (pintype "passive"))
      (node (ref "Q1") (pin "8") (pinfunction "D2b_8") (pintype "passive"))
      (node (ref "Q1") (pin "TAB") (pintype "passive"))
      (node (ref "Q2") (pin "5") (pintype "passive"))
      (node (ref "Q2") (pin "6") (pintype "passive"))
      (node (ref "Q2") (pin "7") (pinfunction "D2a_7") (pintype "passive"))
      (node (ref "Q2") (pin "8") (pinfunction "D2b_8") (pintype "passive"))
      (node (ref "Q2") (pin "TAB") (pintype "passive"))
    )
    (net (code "36") (name "Net-(Q1-G1)") (class "Default")
      (node (ref "Q1") (pin "4") (pinfunction "G1_4") (pintype "passive"))
      (node (ref "R18") (pin "2") (pinfunction "2_2") (pintype "passive"))
      (node (ref "R22") (pin "1") (pinfunction "1_1") (pintype "passive"))
    )
    (net (code "37") (name "Net-(Q2-G1)") (class "Default")
      (node (ref "Q2") (pin "4") (pinfunction "G1_4") (pintype "passive"))
      (node (ref "R19") (pin "2") (pinfunction "2_2") (pintype "passive"))
      (node (ref "R23") (pin "1") (pinfunction "1_1") (pintype "passive"))
    )
    (net (code "38") (name "Net-(Q3-D)") (class "Default")
      (node (ref "Q3") (pin "3") (pinfunction "D_3") (pintype "passive"))
      (node (ref "Q4") (pin "4") (pinfunction "G1_4") (pintype "passive"))
      (node (ref "R26") (pin "2") (pinfunction "2_2") (pintype "passive"))
      (node (ref "R30") (pin "2") (pinfunction "2_2") (pintype "passive"))
    )
    (net (code "39") (name "Net-(Q4-D2a)") (class "Default")
      (node (ref "C26") (pin "2") (pinfunction "2_2") (pintype "passive"))
      (node (ref "C27") (pin "2") (pinfunction "2_2") (pintype "passive"))
      (node (ref "Q4") (pin "5") (pintype "passive"))
      (node (ref "Q4") (pin "6") (pintype "passive"))
      (node (ref "Q4") (pin "7") (pinfunction "D2a_7") (pintype "passive"))
      (node (ref "Q4") (pin "8") (pinfunction "D2b_8") (pintype "passive"))
      (node (ref "Q4") (pin "TAB") (pintype "passive"))
      (node (ref "Q5") (pin "5") (pintype "passive"))
      (node (ref "Q5") (pin "6") (pintype "passive"))
      (node (ref "Q5") (pin "7") (pinfunction "D2a_7") (pintype "passive"))
      (node (ref "Q5") (pin "8") (pinfunction "D2b_8") (pintype "passive"))
      (node (ref "Q5") (pin "TAB") (pintype "passive"))
      (node (ref "R32") (pin "2") (pinfunction "2_2") (pintype "passive"))
    )
    (net (code "40") (name "Net-(R36-I2)") (class "Default")
      (node (ref "L1") (pin "1") (pinfunction "1_1") (pintype "passive"))
      (node (ref "R36") (pin "2") (pinfunction "I2_2") (pintype "passive"))
    )
    (net (code "41") (name "Net-(U1-ACP)") (class "Default")
      (node (ref "R24") (pin "2") (pinfunction "2_2") (pintype "passive"))
      (node (ref "U1") (pin "31") (pinfunction "ACP_31") (pintype "passive"))
    )
    (net (code "42") (name "Net-(U1-CHG)") (class "Default")
      (node (ref "R22") (pin "2") (pinfunction "2_2") (pintype "passive"))
      (node (ref "U1") (pin "32") (pinfunction "CHG_32") (pintype "passive"))
    )
    (net (code "43") (name "Net-(U1-DSG)") (class "Default")
      (node (ref "R23") (pin "2") (pinfunction "2_2") (pintype "passive"))
      (node (ref "U1") (pin "30") (pinfunction "DSG_30") (pintype "passive"))
    )
    (net (code "44") (name "Net-(U1-PBI)") (class "Default")
      (node (ref "C18") (pin "2") (pinfunction "2_2") (pintype "passive"))
      (node (ref "U1") (pin "2") (pinfunction "PBI_2") (pintype "passive"))
    )
    (net (code "45") (name "Net-(U1-SRN)") (class "Default")
      (node (ref "C33") (pin "1") (pinfunction "1_1") (pintype "passive"))
      (node (ref "C34") (pin "1") (pinfunction "1_1") (pintype "passive"))
      (node (ref "R35") (pin "1") (pinfunction "1_1") (pintype "passive"))
      (node (ref "U1") (pin "7") (pinfunction "SRN_7") (pintype "passive"))
    )
    (net (code "46") (name "Net-(U1-SRP)") (class "Default")
      (node (ref "C33") (pin "2") (pinfunction "2_2") (pintype "passive"))
      (node (ref "C34") (pin "2") (pinfunction "2_2") (pintype "passive"))
      (node (ref "R33") (pin "1") (pinfunction "1_1") (pintype "passive"))
      (node (ref "U1") (pin "8") (pinfunction "SRP_8") (pintype "passive"))
    )
    (net (code "47") (name "Net-(U1-VCC)") (class "Default")
      (node (ref "C22") (pin "2") (pinfunction "2_2") (pintype "passive"))
      (node (ref "R32") (pin "1") (pinfunction "1_1") (pintype "passive"))
      (node (ref "U1") (pin "22") (pinfunction "VCC_22") (pintype "passive"))
    )
    (net (code "48") (name "VBAT") (class "Default")
      (node (ref "Q3") (pin "2") (pinfunction "S_2") (pintype "passive"))
      (node (ref "Q4") (pin "1") (pinfunction "S1_1") (pintype "passive"))
      (node (ref "Q4") (pin "2") (pintype "passive"))
      (node (ref "Q4") (pin "3") (pintype "passive"))
      (node (ref "R24") (pin "1") (pinfunction "1_1") (pintype "passive"))
      (node (ref "R26") (pin "1") (pinfunction "1_1") (pintype "passive"))
      (node (ref "R27") (pin "1") (pinfunction "1_1") (pintype "passive"))
      (node (ref "R28") (pin "1") (pinfunction "1_1") (pintype "passive"))
    )
    (net (code "49") (name "VSYS") (class "Default")
      (node (ref "C16") (pin "1") (pinfunction "1_1") (pintype "passive"))
      (node (ref "C36") (pin "1") (pinfunction "1_1") (pintype "passive"))
      (node (ref "C37") (pin "1") (pinfunction "1_1") (pintype "passive"))
      (node (ref "C38") (pin "2") (pinfunction "2_2") (pintype "passive"))
      (node (ref "Q2") (pin "1") (pinfunction "S1_1") (pintype "passive"))
      (node (ref "Q2") (pin "2") (pintype "passive"))
      (node (ref "Q2") (pin "3") (pintype "passive"))
      (node (ref "R19") (pin "1") (pinfunction "1_1") (pintype "passive"))
      (node (ref "R36") (pin "1") (pinfunction "I1_1") (pintype "passive"))
      (node (ref "R37") (pin "1") (pinfunction "1_1") (pintype "passive"))
    )
    (net (code "50") (name "unconnected-(J12-PadMNT)") (class "Default")
      (node (ref "J12") (pin "MNT") (pinfunction "MNT_MNT") (pintype "passive+no_connect"))
    )
    (net (code "51") (name "unconnected-(J13-PadMNT)") (class "Default")
      (node (ref "J13") (pin "MNT") (pinfunction "MNT_MNT") (pintype "passive+no_connect"))
    )
    (net (code "52") (name "unconnected-(J14-PadMNT)") (class "Default")
      (node (ref "J14") (pin "MNT") (pinfunction "MNT_MNT") (pintype "passive+no_connect"))
    )
    (net (code "53") (name "unconnected-(J15-PadMNT)") (class "Default")
      (node (ref "J15") (pin "MNT") (pinfunction "MNT_MNT") (pintype "passive+no_connect"))
    )
  )
)
